# charger_pcb.net
KiCad netlist of a schematic drawn in EAGLE
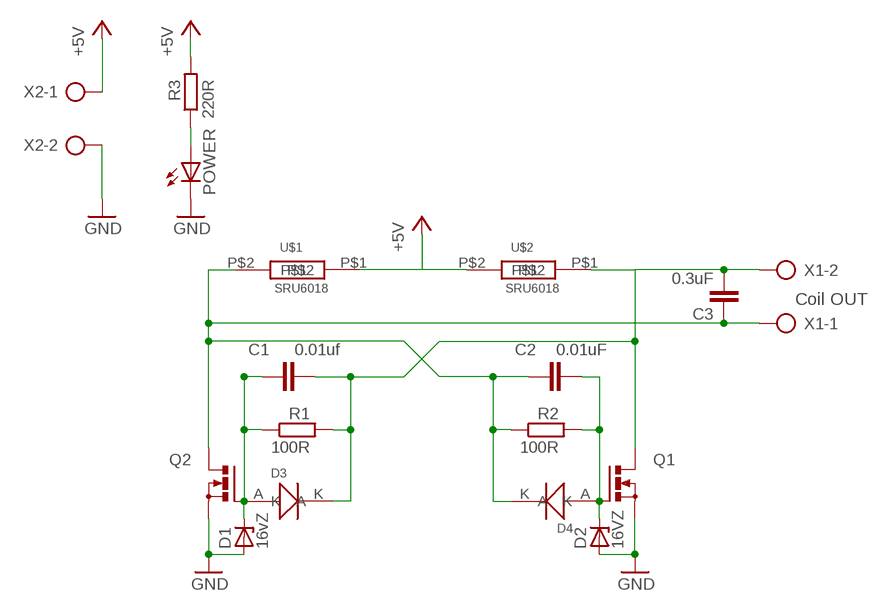
[diagram p0: schematic, sheet 1]

(export (version "E")
  (design (tool "Eeschema 10.0.6"))
  (components
    (comp (ref "C1")
      (value "0.01uf")
      (footprint "eagle-import:C0805")
      (libsource (lib "eagle-import") (part "C-EUC0805"))
    )
    (comp (ref "C2")
      (value "0.01uF")
      (footprint "eagle-import:C0805")
      (libsource (lib "eagle-import") (part "C-EUC0805"))
    )
    (comp (ref "C3")
      (value "0.3uF")
      (footprint "eagle-import:C0805")
      (libsource (lib "eagle-import") (part "C-EUC0805"))
    )
    (comp (ref "D1")
      (value "16vZ")
      (footprint "eagle-import:SOT23")
      (libsource (lib "eagle-import") (part "ZENER-DIODESOT23"))
    )
    (comp (ref "D2")
      (value "16VZ")
      (footprint "eagle-import:SOT23")
      (libsource (lib "eagle-import") (part "ZENER-DIODESOT23"))
    )
    (comp (ref "D3")
      (value "DFLS240L")
      (footprint "eagle-import:POWERDI123")
      (libsource (lib "eagle-import") (part "DFLS240L"))
    )
    (comp (ref "D4")
      (value "DFLS240L")
      (footprint "eagle-import:POWERDI123")
      (libsource (lib "eagle-import") (part "DFLS240L"))
    )
    (comp (ref "POWER")
      (value "LEDCHIP-LED0805")
      (footprint "eagle-import:CHIP-LED0805")
      (libsource (lib "eagle-import") (part "LEDCHIP-LED0805"))
    )
    (comp (ref "Q1")
      (value "N-MOSFET-SO8S")
      (footprint "eagle-import:SO-08")
      (libsource (lib "eagle-import") (part "N-MOSFET-SO8S"))
    )
    (comp (ref "Q2")
      (value "N-MOSFET-SO8S")
      (footprint "eagle-import:SO-08")
      (libsource (lib "eagle-import") (part "N-MOSFET-SO8S"))
    )
    (comp (ref "R1")
      (value "100R")
      (footprint "eagle-import:R0805")
      (libsource (lib "eagle-import") (part "R-EU_R0805"))
    )
    (comp (ref "R2")
      (value "100R")
      (footprint "eagle-import:R0805")
      (libsource (lib "eagle-import") (part "R-EU_R0805"))
    )
    (comp (ref "R3")
      (value "220R")
      (footprint "eagle-import:R0805")
      (libsource (lib "eagle-import") (part "R-EU_R0805"))
    )
    (comp (ref "U$1")
      (value "SRU6018")
      (footprint "eagle-import:SRU6018")
      (libsource (lib "eagle-import") (part "SRU6018"))
    )
    (comp (ref "U$2")
      (value "SRU6018")
      (footprint "eagle-import:SRU6018")
      (libsource (lib "eagle-import") (part "SRU6018"))
    )
    (comp (ref "X1")
      (value "AK500/2")
      (footprint "eagle-import:AK500_2")
      (libsource (lib "eagle-import") (part "AK500/2"))
    )
    (comp (ref "X2")
      (value "AK500/2")
      (footprint "eagle-import:AK500_2")
      (libsource (lib "eagle-import") (part "AK500/2"))
    )
  )
  (nets
    (net (code "1") (name "+5V") (class "Default")
      (node (ref "R3") (pin "2") (pinfunction "2_2") (pintype "passive"))
      (node (ref "U$1") (pin "P$1") (pinfunction "P$1_P$1") (pintype "bidirectional"))
      (node (ref "U$2") (pin "P$2") (pinfunction "P$2_P$2") (pintype "bidirectional"))
      (node (ref "X2") (pin "1") (pinfunction "KL_1") (pintype "passive"))
    )
    (net (code "2") (name "GND") (class "Default")
      (node (ref "D1") (pin "1") (pinfunction "A_1") (pintype "passive"))
      (node (ref "D2") (pin "1") (pinfunction "A_1") (pintype "passive"))
      (node (ref "POWER") (pin "C") (pinfunction "C_C") (pintype "passive"))
      (node (ref "Q1") (pin "1") (pinfunction "S_1") (pintype "passive"))
      (node (ref "Q1") (pin "2") (pinfunction "S_2") (pintype "passive"))
      (node (ref "Q1") (pin "3") (pinfunction "S_3") (pintype "passive"))
      (node (ref "Q2") (pin "1") (pinfunction "S_1") (pintype "passive"))
      (node (ref "Q2") (pin "2") (pinfunction "S_2") (pintype "passive"))
      (node (ref "Q2") (pin "3") (pinfunction "S_3") (pintype "passive"))
      (node (ref "X2") (pin "2") (pinfunction "KL_2") (pintype "passive"))
    )
    (net (code "3") (name "Net-(D1-C)") (class "Default")
      (node (ref "C1") (pin "1") (pinfunction "1_1") (pintype "passive"))
      (node (ref "D1") (pin "3") (pinfunction "C_3") (pintype "passive"))
      (node (ref "D3") (pin "A") (pinfunction "A_A") (pintype "bidirectional"))
      (node (ref "Q2") (pin "4") (pinfunction "G_4") (pintype "passive"))
      (node (ref "R1") (pin "1") (pinfunction "1_1") (pintype "passive"))
    )
    (net (code "4") (name "Net-(D2-C)") (class "Default")
      (node (ref "C2") (pin "2") (pinfunction "2_2") (pintype "passive"))
      (node (ref "D2") (pin "3") (pinfunction "C_3") (pintype "passive"))
      (node (ref "D4") (pin "A") (pinfunction "A_A") (pintype "bidirectional"))
      (node (ref "Q1") (pin "4") (pinfunction "G_4") (pintype "passive"))
      (node (ref "R2") (pin "2") (pinfunction "2_2") (pintype "passive"))
    )
    (net (code "5") (name "Net-(POWER-PadA)") (class "Default")
      (node (ref "POWER") (pin "A") (pinfunction "A_A") (pintype "passive"))
      (node (ref "R3") (pin "1") (pinfunction "1_1") (pintype "passive"))
    )
    (net (code "6") (name "Net-(X1A-KL)") (class "Default")
      (node (ref "C2") (pin "1") (pinfunction "1_1") (pintype "passive"))
      (node (ref "C3") (pin "1") (pinfunction "1_1") (pintype "passive"))
      (node (ref "D4") (pin "K") (pinfunction "K_K") (pintype "bidirectional"))
      (node (ref "Q2") (pin "5") (pinfunction "D_5") (pintype "passive"))
      (node (ref "Q2") (pin "6") (pinfunction "D_6") (pintype "passive"))
      (node (ref "Q2") (pin "7") (pinfunction "D_7") (pintype "passive"))
      (node (ref "Q2") (pin "8") (pinfunction "D_8") (pintype "passive"))
      (node (ref "R2") (pin "1") (pinfunction "1_1") (pintype "passive"))
      (node (ref "U$1") (pin "P$2") (pinfunction "P$2_P$2") (pintype "bidirectional"))
      (node (ref "X1") (pin "1") (pinfunction "KL_1") (pintype "passive"))
    )
    (net (code "7") (name "Net-(X1B-KL)") (class "Default")
      (node (ref "C1") (pin "2") (pinfunction "2_2") (pintype "passive"))
      (node (ref "C3") (pin "2") (pinfunction "2_2") (pintype "passive"))
      (node (ref "D3") (pin "K") (pinfunction "K_K") (pintype "bidirectional"))
      (node (ref "Q1") (pin "5") (pinfunction "D_5") (pintype "passive"))
      (node (ref "Q1") (pin "6") (pinfunction "D_6") (pintype "passive"))
      (node (ref "Q1") (pin "7") (pinfunction "D_7") (pintype "passive"))
      (node (ref "Q1") (pin "8") (pinfunction "D_8") (pintype "passive"))
      (node (ref "R1") (pin "2") (pinfunction "2_2") (pintype "passive"))
      (node (ref "U$2") (pin "P$1") (pinfunction "P$1_P$1") (pintype "bidirectional"))
      (node (ref "X1") (pin "2") (pinfunction "KL_2") (pintype "passive"))
    )
  )
)
